# ContollerRMC.net
KiCad netlist of a schematic drawn in Altium Designer
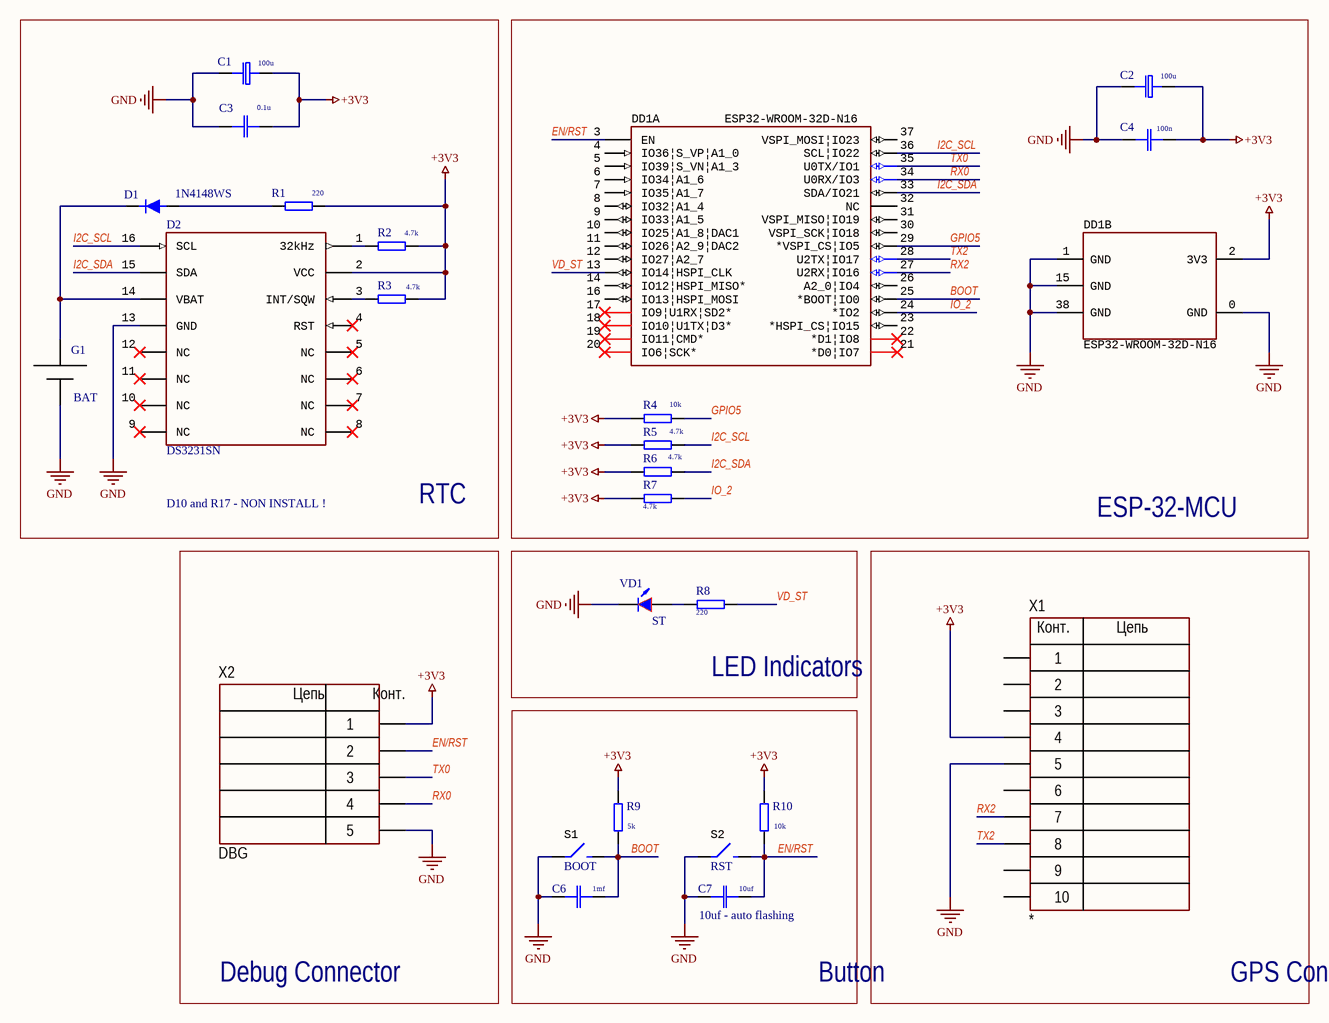
[diagram p0: ContollerRMC.SchDoc]

(export (version "E")
  (design (tool "Eeschema 10.0.6"))
  (components
    (comp (ref "C1")
      (value "100u")
      (footprint "EL Case C (6032-28)")
      (description "TECAP, 100 мкФ, 6.3 В, тип C, 10%")
      (fields (field (name "MANUFACTURER") "Китай") (field (name "PARTNUMBER") "TECAP100/6,3VC, 10%"))
      (libsource (lib "AECorpLB") (part "100u-6.3V"))
    )
    (comp (ref "C2")
      (value "100u")
      (footprint "EL Case C (6032-28)")
      (description "TECAP, 100 мкФ, 6.3 В, тип C, 10%")
      (fields (field (name "MANUFACTURER") "Китай") (field (name "PARTNUMBER") "TECAP100/6,3VC, 10%"))
      (libsource (lib "AECorpLB") (part "100u-6.3V"))
    )
    (comp (ref "C3")
      (value "0.1u")
      (footprint "C0805(2013)")
      (description "SMD-0805")
      (libsource (lib "AECorpLB") (part "C-0805"))
    )
    (comp (ref "C4")
      (value "100n")
      (footprint "C1206(3216)")
      (description "SMD-1206 50V Y5V +80/-20%")
      (libsource (lib "AECorpLB") (part "C-1206   50V 100n"))
    )
    (comp (ref "C6")
      (value "1mf")
      (footprint "C0805(2013)")
      (description "SMD-0805")
      (libsource (lib "AECorpLB") (part "C-0805"))
    )
    (comp (ref "C7")
      (value "10uf")
      (footprint "C0805(2013)")
      (description "SMD-0805")
      (libsource (lib "AECorpLB") (part "C-0805"))
    )
    (comp (ref "D1")
      (value "1N4148WS")
      (footprint "SOD323")
      (description "SOD-323 100V 150mA")
      (libsource (lib "AECorpLB") (part "1N4148WS"))
    )
    (comp (ref "D2")
      (value "DS3231SN")
      (footprint "SO16-300")
      (description "I2C real-time clock (RTC) Integrated  RTC/TCXO/Crystal")
      (fields (field (name "MP") "DS3231") (field (name "MF") "Maxim Integrated Products"))
      (libsource (lib "AECorpLB") (part "DS3231SN"))
    )
    (comp (ref "DD1")
      (value "~")
      (footprint "ESP32-WROOM-32D")
      (description "ESP32-D0WD, Wi-Fi, BLE, 80 - 240MHz")
      (fields (field (name "MANUFACTURER") "Espressif") (field (name "PARTNUMBER") "ESP32-WROOM-32D-N16"))
      (libsource (lib "AECorpLB") (part "ESP32 - WROOM - 32U"))
    )
    (comp (ref "G1")
      (value "BAT")
      (footprint "BAT: BTH-R36-20")
      (description "BATTERY HOLDER COIN CR1220")
      (fields (field (name "MP") "BH1220T-C-G"))
      (libsource (lib "AECorpLB") (part "BATCR1220"))
    )
    (comp (ref "R1")
      (value "220")
      (footprint "R0805")
      (description "SMD 0805 0.1W 5% 150V")
      (libsource (lib "AECorpLB") (part "R-0805"))
    )
    (comp (ref "R2")
      (value "4.7k")
      (footprint "R0805")
      (description "SMD 0805 0.1W 5% 150V")
      (libsource (lib "AECorpLB") (part "R-0805"))
    )
    (comp (ref "R3")
      (value "4.7k")
      (footprint "R0805")
      (description "SMD 0805 0.1W 5% 150V")
      (libsource (lib "AECorpLB") (part "R-0805"))
    )
    (comp (ref "R4")
      (value "10k")
      (footprint "R0805")
      (description "SMD 0805 0.1W 5% 150V")
      (libsource (lib "AECorpLB") (part "R-0805"))
    )
    (comp (ref "R5")
      (value "4.7k")
      (footprint "R0805")
      (description "SMD 0805 0.1W 5% 150V")
      (libsource (lib "AECorpLB") (part "R-0805"))
    )
    (comp (ref "R6")
      (value "4.7k")
      (footprint "R0805")
      (description "SMD 0805 0.1W 5% 150V")
      (libsource (lib "AECorpLB") (part "R-0805"))
    )
    (comp (ref "R7")
      (value "4.7k")
      (footprint "R0805")
      (description "SMD 0805 0.1W 5% 150V")
      (libsource (lib "AECorpLB") (part "R-0805"))
    )
    (comp (ref "R8")
      (value "220")
      (footprint "R0805")
      (description "SMD 0805 0.1W 5% 150V")
      (libsource (lib "AECorpLB") (part "R-0805"))
    )
    (comp (ref "R9")
      (value "5k")
      (footprint "R0805")
      (description "SMD 0805 0.1W 5% 150V")
      (libsource (lib "AECorpLB") (part "R-0805"))
    )
    (comp (ref "R10")
      (value "10k")
      (footprint "R0805")
      (description "SMD 0805 0.1W 5% 150V")
      (libsource (lib "AECorpLB") (part "R-0805"))
    )
    (comp (ref "S1")
      (value "BOOT")
      (footprint "BUT_SKRPACE010")
      (description "SMD Button, 3х4х2.5 mm, 24VDC, 50mA")
      (fields (field (name "PARTNUMBER") "SKRPACE010") (field (name "MANUFACTURER") "ALPS"))
      (libsource (lib "AECorpLB") (part "Button SMD 3х4х2.5"))
    )
    (comp (ref "S2")
      (value "RST")
      (footprint "BUT_SKRPACE010")
      (description "SMD Button, 3х4х2.5 mm, 24VDC, 50mA")
      (fields (field (name "PARTNUMBER") "SKRPACE010") (field (name "MANUFACTURER") "ALPS"))
      (libsource (lib "AECorpLB") (part "Button SMD 3х4х2.5"))
    )
    (comp (ref "VD1")
      (value "ST")
      (footprint "Led 0805-Blue")
      (description "BLUE 247мКд, 120°, 468нМ")
      (libsource (lib "AECorpLB") (part "Led 0805 SMD 2013. TO-2013BC-BF"))
    )
    (comp (ref "X1")
      (value "*")
      (footprint "CON: PLS-10 - 2.0mm")
      (libsource (lib "AECorpLB") (part "10-Connector"))
    )
    (comp (ref "X2") (value "DBG") (footprint "CON: PLS-5") (libsource (lib "AECorpLB") (part "5-Connector")))
  )
  (nets
    (net (code "1") (name "+3V3") (class "Default")
      (node (ref "C1") (pin "1") (pinfunction "1_1") (pintype "passive"))
      (node (ref "C2") (pin "1") (pinfunction "1_1") (pintype "passive"))
      (node (ref "C3") (pin "2") (pinfunction "2_2") (pintype "passive"))
      (node (ref "C4") (pin "1") (pinfunction "1_1") (pintype "passive"))
      (node (ref "D2") (pin "2") (pinfunction "VCC_2") (pintype "power_in"))
      (node (ref "DD1") (pin "2") (pinfunction "3V3_2") (pintype "power_in"))
      (node (ref "R1") (pin "1") (pinfunction "1_1") (pintype "passive"))
      (node (ref "R10") (pin "1") (pinfunction "1_1") (pintype "passive"))
      (node (ref "R2") (pin "2") (pinfunction "2_2") (pintype "passive"))
      (node (ref "R3") (pin "2") (pinfunction "2_2") (pintype "passive"))
      (node (ref "R4") (pin "1") (pinfunction "1_1") (pintype "passive"))
      (node (ref "R5") (pin "1") (pinfunction "1_1") (pintype "passive"))
      (node (ref "R6") (pin "1") (pinfunction "1_1") (pintype "passive"))
      (node (ref "R7") (pin "2") (pinfunction "2_2") (pintype "passive"))
      (node (ref "R9") (pin "1") (pinfunction "1_1") (pintype "passive"))
      (node (ref "X1") (pin "4") (pinfunction "4_4") (pintype "power_in"))
      (node (ref "X2") (pin "1") (pinfunction "1_1") (pintype "passive"))
    )
    (net (code "2") (name "/BOOT") (class "Default")
      (node (ref "C6") (pin "1") (pinfunction "1_1") (pintype "passive"))
      (node (ref "DD1") (pin "25") (pinfunction "*BOOT¦IO0_25") (pintype "bidirectional"))
      (node (ref "R9") (pin "2") (pinfunction "2_2") (pintype "passive"))
      (node (ref "S1") (pin "2") (pinfunction "2_2") (pintype "passive"))
    )
    (net (code "3") (name "/EN{slash}RST") (class "Default")
      (node (ref "C7") (pin "1") (pinfunction "1_1") (pintype "passive"))
      (node (ref "DD1") (pin "3") (pinfunction "EN_3") (pintype "passive"))
      (node (ref "R10") (pin "2") (pinfunction "2_2") (pintype "passive"))
      (node (ref "S2") (pin "2") (pinfunction "2_2") (pintype "passive"))
      (node (ref "X2") (pin "2") (pinfunction "2_2") (pintype "passive"))
    )
    (net (code "4") (name "/GPIO5") (class "Default")
      (node (ref "DD1") (pin "29") (pinfunction "*VSPI_CS¦IO5_29") (pintype "bidirectional"))
      (node (ref "R4") (pin "2") (pinfunction "2_2") (pintype "passive"))
    )
    (net (code "5") (name "/I2C_SCL") (class "Default")
      (node (ref "D2") (pin "16") (pinfunction "SCL_16") (pintype "input"))
      (node (ref "DD1") (pin "36") (pinfunction "SCL¦IO22_36") (pintype "bidirectional"))
      (node (ref "R5") (pin "2") (pinfunction "2_2") (pintype "passive"))
    )
    (net (code "6") (name "/I2C_SDA") (class "Default")
      (node (ref "D2") (pin "15") (pinfunction "SDA_15") (pintype "passive"))
      (node (ref "DD1") (pin "33") (pinfunction "SDA/IO21_33") (pintype "bidirectional"))
      (node (ref "R6") (pin "2") (pinfunction "2_2") (pintype "passive"))
    )
    (net (code "7") (name "/IO_2") (class "Default")
      (node (ref "DD1") (pin "24") (pinfunction "*IO2_24") (pintype "bidirectional"))
      (node (ref "R7") (pin "1") (pinfunction "1_1") (pintype "passive"))
    )
    (net (code "8") (name "/RX0") (class "Default")
      (node (ref "DD1") (pin "34") (pinfunction "U0RX/IO3_34") (pintype "bidirectional"))
      (node (ref "X2") (pin "4") (pinfunction "4_4") (pintype "power_in"))
    )
    (net (code "9") (name "/RX2") (class "Default")
      (node (ref "DD1") (pin "27") (pinfunction "U2RX¦IO16_27") (pintype "bidirectional"))
      (node (ref "X1") (pin "7") (pinfunction "7_7") (pintype "power_in"))
    )
    (net (code "10") (name "/TX0") (class "Default")
      (node (ref "DD1") (pin "35") (pinfunction "U0TX/IO1_35") (pintype "bidirectional"))
      (node (ref "X2") (pin "3") (pinfunction "3_3") (pintype "power_in"))
    )
    (net (code "11") (name "/TX2") (class "Default")
      (node (ref "DD1") (pin "28") (pinfunction "U2TX¦IO17_28") (pintype "bidirectional"))
      (node (ref "X1") (pin "8") (pinfunction "8_8") (pintype "power_in"))
    )
    (net (code "12") (name "/VD_ST") (class "Default")
      (node (ref "DD1") (pin "13") (pinfunction "IO14¦HSPI_CLK_13") (pintype "bidirectional"))
      (node (ref "R8") (pin "2") (pinfunction "2_2") (pintype "passive"))
    )
    (net (code "13") (name "GND") (class "Default")
      (node (ref "C1") (pin "2") (pinfunction "2_2") (pintype "passive"))
      (node (ref "C2") (pin "2") (pinfunction "2_2") (pintype "passive"))
      (node (ref "C3") (pin "1") (pinfunction "1_1") (pintype "passive"))
      (node (ref "C4") (pin "2") (pinfunction "2_2") (pintype "passive"))
      (node (ref "C6") (pin "2") (pinfunction "2_2") (pintype "passive"))
      (node (ref "C7") (pin "2") (pinfunction "2_2") (pintype "passive"))
      (node (ref "D2") (pin "13") (pinfunction "GND_13") (pintype "power_in"))
      (node (ref "DD1") (pin "0") (pinfunction "GND_0") (pintype "power_in"))
      (node (ref "DD1") (pin "1") (pinfunction "GND_1") (pintype "power_in"))
      (node (ref "DD1") (pin "15") (pinfunction "GND_15") (pintype "power_in"))
      (node (ref "DD1") (pin "38") (pinfunction "GND_38") (pintype "power_in"))
      (node (ref "G1") (pin "2") (pinfunction "-_2") (pintype "passive"))
      (node (ref "S1") (pin "1") (pinfunction "1_1") (pintype "passive"))
      (node (ref "S2") (pin "1") (pinfunction "1_1") (pintype "passive"))
      (node (ref "VD1") (pin "2") (pinfunction "K_2") (pintype "passive"))
      (node (ref "X1") (pin "5") (pinfunction "5_5") (pintype "power_in"))
      (node (ref "X2") (pin "5") (pinfunction "5_5") (pintype "power_in"))
    )
    (net (code "14") (name "Net-(D1-A)") (class "Default")
      (node (ref "D1") (pin "1") (pinfunction "A_1") (pintype "passive"))
      (node (ref "R1") (pin "2") (pinfunction "2_2") (pintype "passive"))
    )
    (net (code "15") (name "Net-(D1-C)") (class "Default")
      (node (ref "D1") (pin "2") (pinfunction "C_2") (pintype "passive"))
      (node (ref "D2") (pin "14") (pinfunction "VBAT_14") (pintype "power_in"))
      (node (ref "G1") (pin "1") (pinfunction "+_1") (pintype "passive"))
    )
    (net (code "16") (name "Net-(D2-32kHz)") (class "Default")
      (node (ref "D2") (pin "1") (pinfunction "32kHz_1") (pintype "output"))
      (node (ref "R2") (pin "1") (pinfunction "1_1") (pintype "passive"))
    )
    (net (code "17") (name "Net-(D2-INT{slash}SQW)") (class "Default")
      (node (ref "D2") (pin "3") (pinfunction "INT/SQW_3") (pintype "input"))
      (node (ref "R3") (pin "1") (pinfunction "1_1") (pintype "passive"))
    )
    (net (code "18") (name "Net-(VD1-A)") (class "Default")
      (node (ref "R8") (pin "1") (pinfunction "1_1") (pintype "passive"))
      (node (ref "VD1") (pin "1") (pinfunction "A_1") (pintype "passive"))
    )
    (net (code "19") (name "unconnected-(D2-NC-Pad5)") (class "Default")
      (node (ref "D2") (pin "5") (pinfunction "NC_5") (pintype "passive+no_connect"))
    )
    (net (code "20") (name "unconnected-(D2-NC-Pad6)") (class "Default")
      (node (ref "D2") (pin "6") (pinfunction "NC_6") (pintype "passive+no_connect"))
    )
    (net (code "21") (name "unconnected-(D2-NC-Pad7)") (class "Default")
      (node (ref "D2") (pin "7") (pinfunction "NC_7") (pintype "passive+no_connect"))
    )
    (net (code "22") (name "unconnected-(D2-NC-Pad8)") (class "Default")
      (node (ref "D2") (pin "8") (pinfunction "NC_8") (pintype "passive+no_connect"))
    )
    (net (code "23") (name "unconnected-(D2-NC-Pad9)") (class "Default")
      (node (ref "D2") (pin "9") (pinfunction "NC_9") (pintype "passive+no_connect"))
    )
    (net (code "24") (name "unconnected-(D2-NC-Pad10)") (class "Default")
      (node (ref "D2") (pin "10") (pinfunction "NC_10") (pintype "passive+no_connect"))
    )
    (net (code "25") (name "unconnected-(D2-NC-Pad11)") (class "Default")
      (node (ref "D2") (pin "11") (pinfunction "NC_11") (pintype "passive+no_connect"))
    )
    (net (code "26") (name "unconnected-(D2-NC-Pad12)") (class "Default")
      (node (ref "D2") (pin "12") (pinfunction "NC_12") (pintype "passive+no_connect"))
    )
    (net (code "27") (name "unconnected-(D2-RST-Pad4)") (class "Default")
      (node (ref "D2") (pin "4") (pinfunction "RST_4") (pintype "input+no_connect"))
    )
    (net (code "28") (name "unconnected-(DD1A-*D0¦IO7-Pad21)") (class "Default")
      (node (ref "DD1") (pin "21") (pinfunction "*D0¦IO7_21") (pintype "passive+no_connect"))
    )
    (net (code "29") (name "unconnected-(DD1A-*D1¦IO8-Pad22)") (class "Default")
      (node (ref "DD1") (pin "22") (pinfunction "*D1¦IO8_22") (pintype "passive+no_connect"))
    )
    (net (code "30") (name "unconnected-(DD1A-*HSPI_CS¦IO15-Pad23)") (class "Default")
      (node (ref "DD1") (pin "23") (pinfunction "*HSPI_CS¦IO15_23") (pintype "bidirectional"))
    )
    (net (code "31") (name "unconnected-(DD1A-A2_0¦IO4-Pad26)") (class "Default")
      (node (ref "DD1") (pin "26") (pinfunction "A2_0¦IO4_26") (pintype "bidirectional"))
    )
    (net (code "32") (name "unconnected-(DD1A-IO6¦SCK*-Pad20)") (class "Default")
      (node (ref "DD1") (pin "20") (pinfunction "IO6¦SCK*_20") (pintype "passive+no_connect"))
    )
    (net (code "33") (name "unconnected-(DD1A-IO9¦U1RX¦SD2*-Pad17)") (class "Default")
      (node (ref "DD1") (pin "17") (pinfunction "IO9¦U1RX¦SD2*_17") (pintype "passive+no_connect"))
    )
    (net (code "34") (name "unconnected-(DD1A-IO10¦U1TX¦D3*-Pad18)") (class "Default")
      (node (ref "DD1") (pin "18") (pinfunction "IO10¦U1TX¦D3*_18") (pintype "passive+no_connect"))
    )
    (net (code "35") (name "unconnected-(DD1A-IO11¦CMD*-Pad19)") (class "Default")
      (node (ref "DD1") (pin "19") (pinfunction "IO11¦CMD*_19") (pintype "passive+no_connect"))
    )
    (net (code "36") (name "unconnected-(DD1A-IO12¦HSPI_MISO*-Pad14)") (class "Default")
      (node (ref "DD1") (pin "14") (pinfunction "IO12¦HSPI_MISO*_14") (pintype "bidirectional"))
    )
    (net (code "37") (name "unconnected-(DD1A-IO13¦HSPI_MOSI-Pad16)") (class "Default")
      (node (ref "DD1") (pin "16") (pinfunction "IO13¦HSPI_MOSI_16") (pintype "bidirectional"))
    )
    (net (code "38") (name "unconnected-(DD1A-IO25¦A1_8¦DAC1-Pad10)") (class "Default")
      (node (ref "DD1") (pin "10") (pinfunction "IO25¦A1_8¦DAC1_10") (pintype "bidirectional"))
    )
    (net (code "39") (name "unconnected-(DD1A-IO26¦A2_9¦DAC2-Pad11)") (class "Default")
      (node (ref "DD1") (pin "11") (pinfunction "IO26¦A2_9¦DAC2_11") (pintype "bidirectional"))
    )
    (net (code "40") (name "unconnected-(DD1A-IO27¦A2_7-Pad12)") (class "Default")
      (node (ref "DD1") (pin "12") (pinfunction "IO27¦A2_7_12") (pintype "bidirectional"))
    )
    (net (code "41") (name "unconnected-(DD1A-IO32¦A1_4-Pad8)") (class "Default")
      (node (ref "DD1") (pin "8") (pinfunction "IO32¦A1_4_8") (pintype "bidirectional"))
    )
    (net (code "42") (name "unconnected-(DD1A-IO33¦A1_5-Pad9)") (class "Default")
      (node (ref "DD1") (pin "9") (pinfunction "IO33¦A1_5_9") (pintype "bidirectional"))
    )
    (net (code "43") (name "unconnected-(DD1A-IO34¦A1_6-Pad6)") (class "Default")
      (node (ref "DD1") (pin "6") (pinfunction "IO34¦A1_6_6") (pintype "input"))
    )
    (net (code "44") (name "unconnected-(DD1A-IO35¦A1_7-Pad7)") (class "Default")
      (node (ref "DD1") (pin "7") (pinfunction "IO35¦A1_7_7") (pintype "input"))
    )
    (net (code "45") (name "unconnected-(DD1A-IO36¦S_VP¦A1_0-Pad4)") (class "Default")
      (node (ref "DD1") (pin "4") (pinfunction "IO36¦S_VP¦A1_0_4") (pintype "input"))
    )
    (net (code "46") (name "unconnected-(DD1A-IO39¦S_VN¦A1_3-Pad5)") (class "Default")
      (node (ref "DD1") (pin "5") (pinfunction "IO39¦S_VN¦A1_3_5") (pintype "input"))
    )
    (net (code "47") (name "unconnected-(DD1A-NC-Pad32)") (class "Default")
      (node (ref "DD1") (pin "32") (pinfunction "NC_32") (pintype "passive"))
    )
    (net (code "48") (name "unconnected-(DD1A-VSPI_MISO¦IO19-Pad31)") (class "Default")
      (node (ref "DD1") (pin "31") (pinfunction "VSPI_MISO¦IO19_31") (pintype "bidirectional"))
    )
    (net (code "49") (name "unconnected-(DD1A-VSPI_MOSI¦IO23-Pad37)") (class "Default")
      (node (ref "DD1") (pin "37") (pinfunction "VSPI_MOSI¦IO23_37") (pintype "bidirectional"))
    )
    (net (code "50") (name "unconnected-(DD1A-VSPI_SCK¦IO18-Pad30)") (class "Default")
      (node (ref "DD1") (pin "30") (pinfunction "VSPI_SCK¦IO18_30") (pintype "bidirectional"))
    )
    (net (code "51") (name "unconnected-(X1-Pad1)") (class "Default")
      (node (ref "X1") (pin "1") (pinfunction "1_1") (pintype "passive"))
    )
    (net (code "52") (name "unconnected-(X1-Pad2)") (class "Default")
      (node (ref "X1") (pin "2") (pinfunction "2_2") (pintype "passive"))
    )
    (net (code "53") (name "unconnected-(X1-Pad3)") (class "Default")
      (node (ref "X1") (pin "3") (pinfunction "3_3") (pintype "power_in"))
    )
    (net (code "54") (name "unconnected-(X1-Pad6)") (class "Default")
      (node (ref "X1") (pin "6") (pinfunction "6_6") (pintype "power_in"))
    )
    (net (code "55") (name "unconnected-(X1-Pad9)") (class "Default")
      (node (ref "X1") (pin "9") (pinfunction "9_9") (pintype "power_in"))
    )
    (net (code "56") (name "unconnected-(X1-Pad10)") (class "Default")
      (node (ref "X1") (pin "10") (pinfunction "10_10") (pintype "power_in"))
    )
  )
)
